# AutomatonXL320.net
KiCad netlist of a schematic drawn in EAGLE
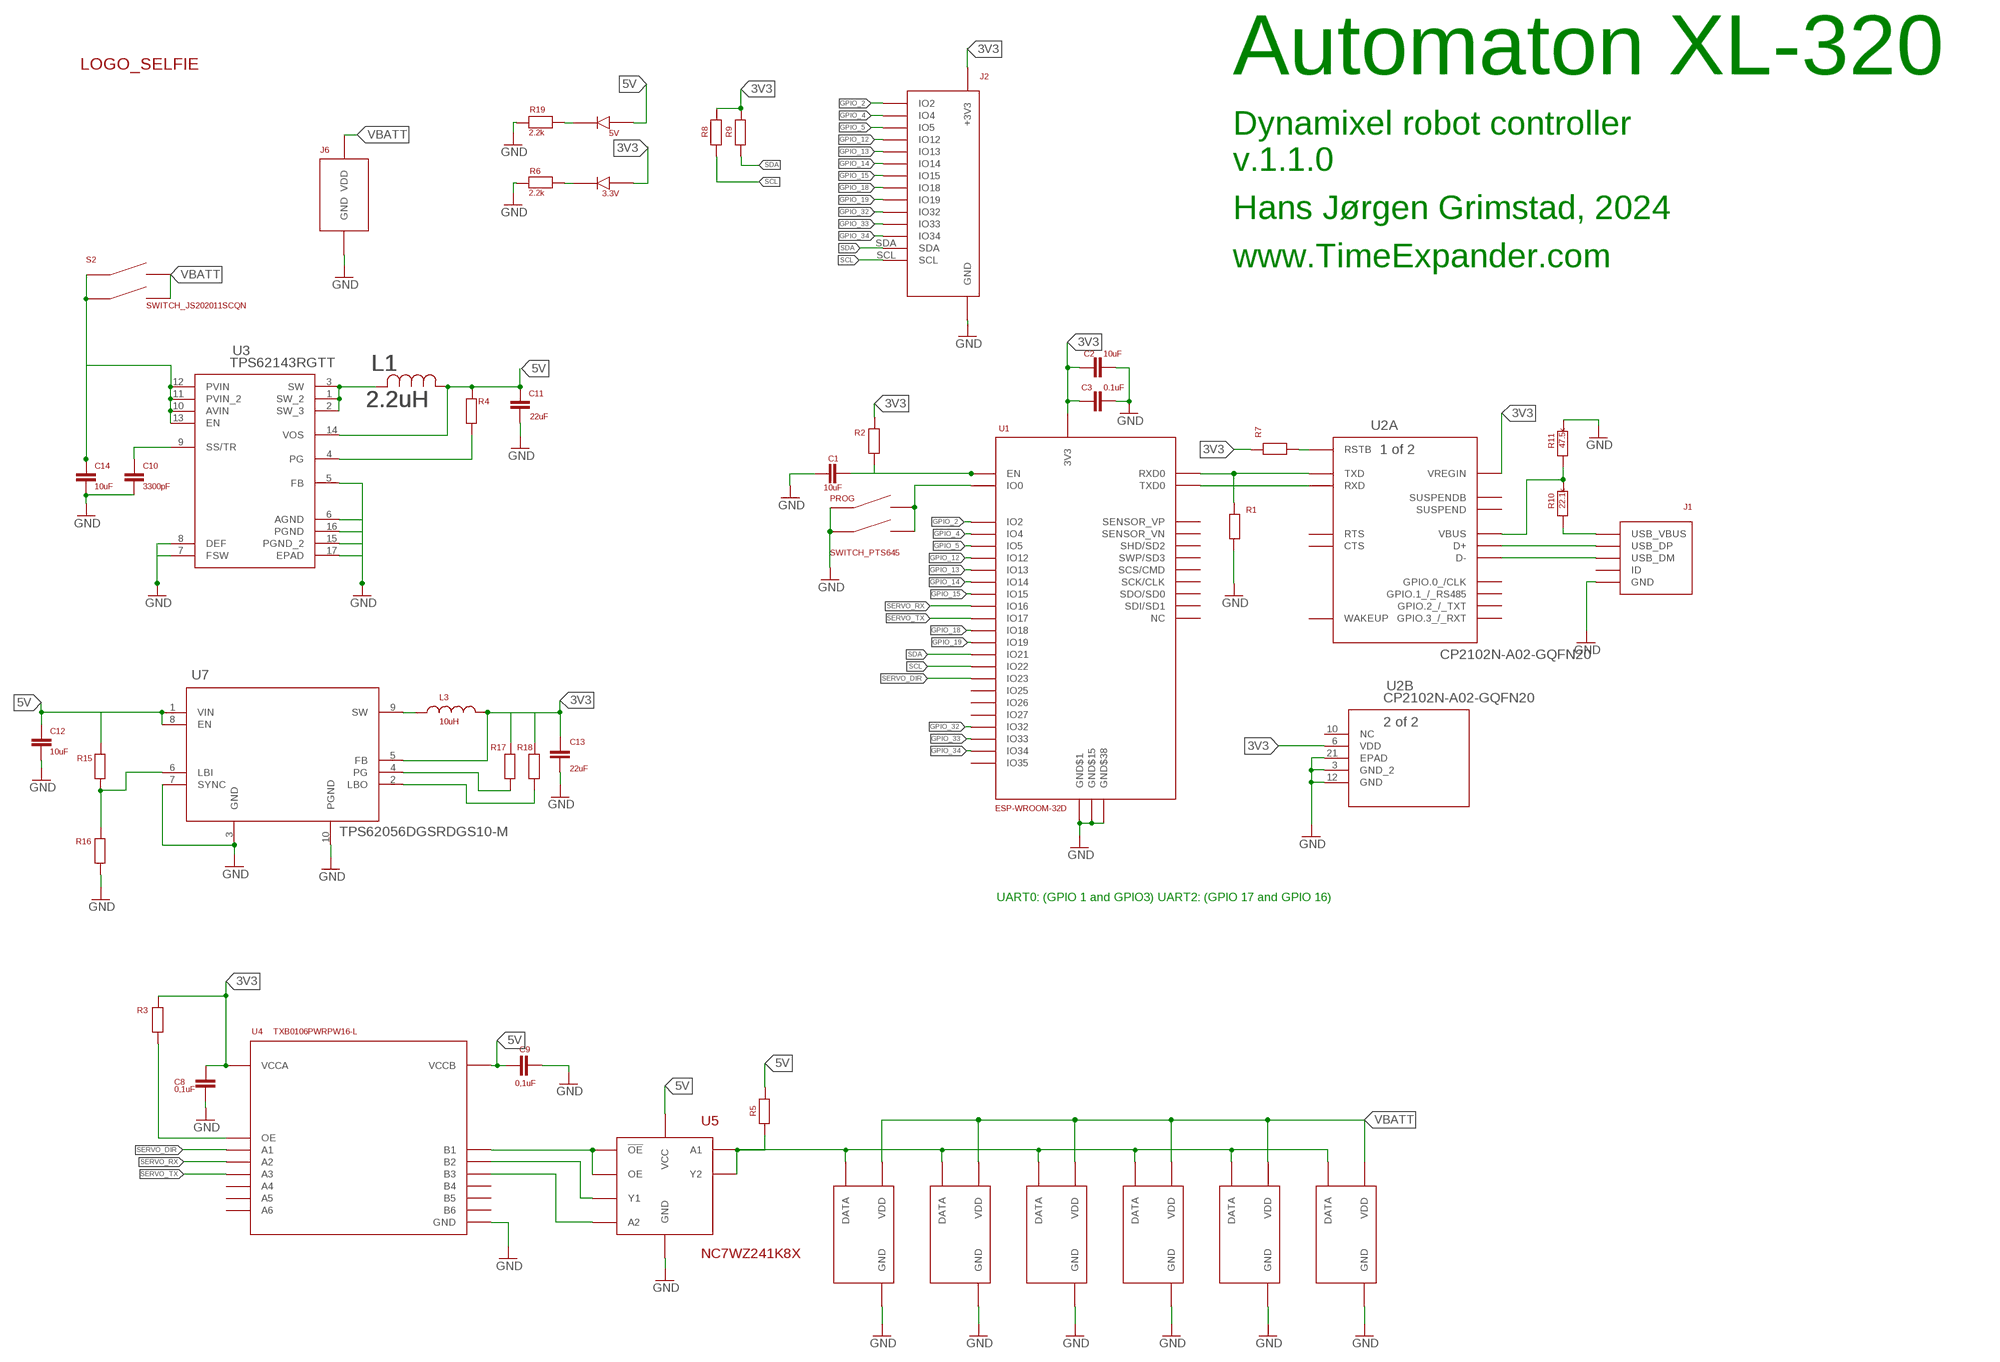
[diagram p0: schematic, sheet 1]

(export (version "E")
  (design (tool "Eeschema 10.0.6"))
  (components
    (comp (ref "3.3V")
      (value "LED_APTR3216PBC/A")
      (footprint "eagle-import:LED_APTR3216PBC_A")
      (libsource (lib "eagle-import") (part "LED_APTR3216PBC/A"))
    )
    (comp (ref "5V")
      (value "LED_APTR3216PBC/A")
      (footprint "eagle-import:LED_APTR3216PBC_A")
      (libsource (lib "eagle-import") (part "LED_APTR3216PBC/A"))
    )
    (comp (ref "C1")
      (value "10uF")
      (footprint "eagle-import:CAP_0402")
      (libsource (lib "eagle-import") (part "CAPACITOR0402"))
    )
    (comp (ref "C2")
      (value "10uF")
      (footprint "eagle-import:CAP_0402")
      (libsource (lib "eagle-import") (part "CAPACITOR0402"))
    )
    (comp (ref "C3")
      (value "0.1uF")
      (footprint "eagle-import:CAP_0402")
      (libsource (lib "eagle-import") (part "CAPACITOR0402"))
    )
    (comp (ref "C8")
      (value "0,1uF")
      (footprint "eagle-import:CAP_0402")
      (libsource (lib "eagle-import") (part "CAPACITOR0402"))
    )
    (comp (ref "C9")
      (value "0,1uF")
      (footprint "eagle-import:CAP_0402")
      (libsource (lib "eagle-import") (part "CAPACITOR0402"))
    )
    (comp (ref "C10")
      (value "3300pF")
      (footprint "eagle-import:CAP_0402")
      (libsource (lib "eagle-import") (part "CAPACITOR0402"))
    )
    (comp (ref "C11")
      (value "22uF")
      (footprint "eagle-import:CAP_1206")
      (libsource (lib "eagle-import") (part "CAPACITOR1206"))
    )
    (comp (ref "C12")
      (value "10uF")
      (footprint "eagle-import:CAP_1206")
      (libsource (lib "eagle-import") (part "CAPACITOR1206"))
    )
    (comp (ref "C13")
      (value "22uF")
      (footprint "eagle-import:CAP_1206")
      (libsource (lib "eagle-import") (part "CAPACITOR1206"))
    )
    (comp (ref "C14")
      (value "10uF")
      (footprint "eagle-import:CAP_1206")
      (libsource (lib "eagle-import") (part "CAPACITOR1206"))
    )
    (comp (ref "J1")
      (value "USB_RCPT_10118192-0001LF")
      (footprint "eagle-import:USB_RCPT_10118192-0001LF")
      (libsource (lib "eagle-import") (part "USB_RCPT_10118192-0001LF"))
    )
    (comp (ref "J2")
      (value "ESP_ROBOT_BOARD_GPIO_16")
      (footprint "eagle-import:ESP_ROBOT_BOARD_GPIO_16")
      (libsource (lib "eagle-import") (part "ESP_ROBOT_BOARD_GPIO_16"))
    )
    (comp (ref "J6")
      (value "BATTERY")
      (footprint "eagle-import:BATTERY_SOLDER_TERMINAL")
      (libsource (lib "eagle-import") (part "POWER_SOLDER_TERMINAL9V"))
    )
    (comp (ref "L1")
      (value "2.2uH")
      (footprint "eagle-import:IND_IHLP-1616AB-M")
      (fields (field (name "MANUFACTURER_PART_NUMBER") "IHLP1616ABER2R2M11"))
      (libsource (lib "eagle-import") (part "IHLP1616ABER2R2M11IND_IHLP-1616AB-M"))
    )
    (comp (ref "L3")
      (value "10uH")
      (footprint "eagle-import:IND_4028")
      (libsource (lib "eagle-import") (part "INDUCTOR_VLCF4024T-100MR90-2"))
    )
    (comp (ref "PROG")
      (value "SWITCH_PTS645")
      (footprint "eagle-import:SWITCH_PTS645_EE_NBIOT_01")
      (libsource (lib "eagle-import") (part "SWITCH_PTS645"))
    )
    (comp (ref "R1")
      (value "RESISTOR0402")
      (footprint "eagle-import:RES_0402")
      (libsource (lib "eagle-import") (part "RESISTOR0402"))
    )
    (comp (ref "R2")
      (value "RESISTOR0402")
      (footprint "eagle-import:RES_0402")
      (libsource (lib "eagle-import") (part "RESISTOR0402"))
    )
    (comp (ref "R3")
      (value "RESISTOR0402")
      (footprint "eagle-import:RES_0402")
      (libsource (lib "eagle-import") (part "RESISTOR0402"))
    )
    (comp (ref "R4")
      (value "RESISTOR0402")
      (footprint "eagle-import:RES_0402")
      (libsource (lib "eagle-import") (part "RESISTOR0402"))
    )
    (comp (ref "R5")
      (value "RESISTOR0402")
      (footprint "eagle-import:RES_0402")
      (libsource (lib "eagle-import") (part "RESISTOR0402"))
    )
    (comp (ref "R6")
      (value "2.2k")
      (footprint "eagle-import:RES_0402")
      (libsource (lib "eagle-import") (part "RESISTOR"))
    )
    (comp (ref "R7")
      (value "RESISTOR0402")
      (footprint "eagle-import:RES_0402")
      (libsource (lib "eagle-import") (part "RESISTOR0402"))
    )
    (comp (ref "R8")
      (value "RESISTOR0402")
      (footprint "eagle-import:RES_0402")
      (libsource (lib "eagle-import") (part "RESISTOR0402"))
    )
    (comp (ref "R9")
      (value "RESISTOR0402")
      (footprint "eagle-import:RES_0402")
      (libsource (lib "eagle-import") (part "RESISTOR0402"))
    )
    (comp (ref "R10")
      (value "22.1k")
      (footprint "eagle-import:RES_0402")
      (libsource (lib "eagle-import") (part "RESISTOR0402"))
    )
    (comp (ref "R11")
      (value "47.5k")
      (footprint "eagle-import:RES_0402")
      (libsource (lib "eagle-import") (part "RESISTOR0402"))
    )
    (comp (ref "R15")
      (value "RESISTOR0402")
      (footprint "eagle-import:RES_0402")
      (libsource (lib "eagle-import") (part "RESISTOR0402"))
    )
    (comp (ref "R16")
      (value "RESISTOR0402")
      (footprint "eagle-import:RES_0402")
      (libsource (lib "eagle-import") (part "RESISTOR0402"))
    )
    (comp (ref "R17")
      (value "RESISTOR0402")
      (footprint "eagle-import:RES_0402")
      (libsource (lib "eagle-import") (part "RESISTOR0402"))
    )
    (comp (ref "R18")
      (value "RESISTOR0402")
      (footprint "eagle-import:RES_0402")
      (libsource (lib "eagle-import") (part "RESISTOR0402"))
    )
    (comp (ref "R19")
      (value "2.2k")
      (footprint "eagle-import:RES_0402")
      (libsource (lib "eagle-import") (part "RESISTOR"))
    )
    (comp (ref "S2")
      (value "SWITCH_JS202011SCQN")
      (footprint "eagle-import:SWITCH_JS202011SCQN")
      (libsource (lib "eagle-import") (part "SWITCH_JS202011SCQN"))
    )
    (comp (ref "U$1")
      (value "DYNAMIXEL_MOLEX_MINISPOX_3P_HEADERXL-320")
      (footprint "eagle-import:DYNAMIXEL_MICROLATCH_3P_HEADER")
      (libsource (lib "eagle-import") (part "DYNAMIXEL_MOLEX_MINISPOX_3P_HEADERXL-320"))
    )
    (comp (ref "U$2")
      (value "LOGO_SELFIESELFIE_2")
      (footprint "eagle-import:TIMEEXPANDER_LOGO_1")
      (libsource (lib "eagle-import") (part "LOGO_SELFIESELFIE_2"))
    )
    (comp (ref "U$4")
      (value "DYNAMIXEL_MOLEX_MINISPOX_3P_HEADERXL-320")
      (footprint "eagle-import:DYNAMIXEL_MICROLATCH_3P_HEADER")
      (libsource (lib "eagle-import") (part "DYNAMIXEL_MOLEX_MINISPOX_3P_HEADERXL-320"))
    )
    (comp (ref "U$5")
      (value "DYNAMIXEL_MOLEX_MINISPOX_3P_HEADERXL-320")
      (footprint "eagle-import:DYNAMIXEL_MICROLATCH_3P_HEADER")
      (libsource (lib "eagle-import") (part "DYNAMIXEL_MOLEX_MINISPOX_3P_HEADERXL-320"))
    )
    (comp (ref "U$6")
      (value "DYNAMIXEL_MOLEX_MINISPOX_3P_HEADERXL-320")
      (footprint "eagle-import:DYNAMIXEL_MICROLATCH_3P_HEADER")
      (libsource (lib "eagle-import") (part "DYNAMIXEL_MOLEX_MINISPOX_3P_HEADERXL-320"))
    )
    (comp (ref "U$8")
      (value "DYNAMIXEL_MOLEX_MINISPOX_3P_HEADERXL-320")
      (footprint "eagle-import:DYNAMIXEL_MICROLATCH_3P_HEADER")
      (libsource (lib "eagle-import") (part "DYNAMIXEL_MOLEX_MINISPOX_3P_HEADERXL-320"))
    )
    (comp (ref "U$9")
      (value "DYNAMIXEL_MOLEX_MINISPOX_3P_HEADERXL-320")
      (footprint "eagle-import:DYNAMIXEL_MICROLATCH_3P_HEADER")
      (libsource (lib "eagle-import") (part "DYNAMIXEL_MOLEX_MINISPOX_3P_HEADERXL-320"))
    )
    (comp (ref "U1")
      (value "ESP-WROOM-32D")
      (footprint "eagle-import:ESP_WROOM_32D")
      (libsource (lib "eagle-import") (part "ESP-WROOM-32D"))
    )
    (comp (ref "U2")
      (value "CP2102N-A02-GQFN20")
      (footprint "eagle-import:QFN20_CP2102N_SIL")
      (fields (field (name "COPYRIGHT") "Copyright (C) 2023 Ultra Librarian. All rights reserved."))
      (libsource (lib "eagle-import") (part "CP2102N-A02-GQFN20"))
    )
    (comp (ref "U3")
      (value "TPS62143RGTT")
      (footprint "eagle-import:RGT16_1P7X1P7")
      (fields (field (name "MANUFACTURER") "Texas Instruments"))
      (libsource (lib "eagle-import") (part "TPS62143RGTT"))
    )
    (comp (ref "U4")
      (value "TXB0106PWRPW16-L")
      (footprint "eagle-import:PW16-L")
      (fields (field (name "MANUFACTURER_PART_NUMBER") "TXB0106PWR"))
      (libsource (lib "eagle-import") (part "TXB0106PWRPW16-L"))
    )
    (comp (ref "U5")
      (value "NC7WZ241K8X")
      (footprint "eagle-import:NC7WZ241K8X")
      (libsource (lib "eagle-import") (part "NC7WZ241K8X"))
    )
    (comp (ref "U7")
      (value "TPS62056DGSRDGS10-M")
      (footprint "eagle-import:DGS10-M")
      (fields
        (field (name "MANUFACTURER") "Texas Instruments")
        (field (name "MANUFACTURER_PART_NUMBER") "TPS62056DGSR")
      )
      (libsource (lib "eagle-import") (part "TPS62056DGSRDGS10-M"))
    )
  )
  (nets
    (net (code "1") (name "3V3") (class "Default")
      (node (ref "3.3V") (pin "A") (pinfunction "A_A") (pintype "passive"))
      (node (ref "C13") (pin "P$1") (pinfunction "1_P$1") (pintype "passive"))
      (node (ref "C2") (pin "P$1") (pinfunction "1_P$1") (pintype "passive"))
      (node (ref "C3") (pin "P$1") (pinfunction "1_P$1") (pintype "passive"))
      (node (ref "C8") (pin "P$2") (pinfunction "2_P$2") (pintype "passive"))
      (node (ref "J2") (pin "+3V3") (pinfunction "+3V3_+3V3") (pintype "bidirectional"))
      (node (ref "L3") (pin "2") (pinfunction "2_2") (pintype "passive"))
      (node (ref "R17") (pin "P$2") (pinfunction "P$2_P$2") (pintype "bidirectional"))
      (node (ref "R18") (pin "P$2") (pinfunction "P$2_P$2") (pintype "bidirectional"))
      (node (ref "R2") (pin "P$2") (pinfunction "P$2_P$2") (pintype "bidirectional"))
      (node (ref "R3") (pin "P$2") (pinfunction "P$2_P$2") (pintype "bidirectional"))
      (node (ref "R7") (pin "P$1") (pinfunction "P$1_P$1") (pintype "bidirectional"))
      (node (ref "R8") (pin "P$2") (pinfunction "P$2_P$2") (pintype "bidirectional"))
      (node (ref "R9") (pin "P$2") (pinfunction "P$2_P$2") (pintype "bidirectional"))
      (node (ref "U1") (pin "2") (pinfunction "3V3_2") (pintype "bidirectional"))
      (node (ref "U2") (pin "6") (pinfunction "VDD_6") (pintype "power_in"))
      (node (ref "U2") (pin "7") (pinfunction "VREGIN_7") (pintype "passive"))
      (node (ref "U4") (pin "2") (pinfunction "VCCA_2") (pintype "power_in"))
      (node (ref "U7") (pin "5") (pinfunction "FB_5") (pintype "input"))
    )
    (net (code "2") (name "5V") (class "Default")
      (node (ref "5V") (pin "A") (pinfunction "A_A") (pintype "passive"))
      (node (ref "C11") (pin "P$1") (pinfunction "1_P$1") (pintype "passive"))
      (node (ref "C12") (pin "P$1") (pinfunction "1_P$1") (pintype "passive"))
      (node (ref "C9") (pin "P$1") (pinfunction "1_P$1") (pintype "passive"))
      (node (ref "L1") (pin "1") (pinfunction "1_1") (pintype "passive"))
      (node (ref "R15") (pin "P$2") (pinfunction "P$2_P$2") (pintype "bidirectional"))
      (node (ref "R4") (pin "P$2") (pinfunction "P$2_P$2") (pintype "bidirectional"))
      (node (ref "R5") (pin "P$2") (pinfunction "P$2_P$2") (pintype "bidirectional"))
      (node (ref "U3") (pin "14") (pinfunction "VOS_14") (pintype "input"))
      (node (ref "U4") (pin "15") (pinfunction "VCCB_15") (pintype "power_in"))
      (node (ref "U5") (pin "VCC") (pinfunction "VCC_VCC") (pintype "power_in"))
      (node (ref "U7") (pin "1") (pinfunction "VIN_1") (pintype "input"))
      (node (ref "U7") (pin "8") (pinfunction "EN_8") (pintype "input"))
    )
    (net (code "3") (name "GND") (class "Default")
      (node (ref "C1") (pin "P$1") (pinfunction "1_P$1") (pintype "passive"))
      (node (ref "C10") (pin "P$2") (pinfunction "2_P$2") (pintype "passive"))
      (node (ref "C11") (pin "P$2") (pinfunction "2_P$2") (pintype "passive"))
      (node (ref "C12") (pin "P$2") (pinfunction "2_P$2") (pintype "passive"))
      (node (ref "C13") (pin "P$2") (pinfunction "2_P$2") (pintype "passive"))
      (node (ref "C14") (pin "P$2") (pinfunction "2_P$2") (pintype "passive"))
      (node (ref "C2") (pin "P$2") (pinfunction "2_P$2") (pintype "passive"))
      (node (ref "C3") (pin "P$2") (pinfunction "2_P$2") (pintype "passive"))
      (node (ref "C8") (pin "P$1") (pinfunction "1_P$1") (pintype "passive"))
      (node (ref "C9") (pin "P$2") (pinfunction "2_P$2") (pintype "passive"))
      (node (ref "J1") (pin "GND") (pinfunction "GND_GND") (pintype "passive"))
      (node (ref "J2") (pin "GND") (pinfunction "GND_GND") (pintype "bidirectional"))
      (node (ref "J6") (pin "-") (pinfunction "GND_-") (pintype "bidirectional"))
      (node (ref "PROG") (pin "A1") (pinfunction "A1_A1") (pintype "bidirectional"))
      (node (ref "PROG") (pin "A2") (pinfunction "A2_A2") (pintype "bidirectional"))
      (node (ref "R1") (pin "P$2") (pinfunction "P$2_P$2") (pintype "bidirectional"))
      (node (ref "R11") (pin "P$2") (pinfunction "P$2_P$2") (pintype "bidirectional"))
      (node (ref "R16") (pin "P$1") (pinfunction "P$1_P$1") (pintype "bidirectional"))
      (node (ref "R19") (pin "P$1") (pinfunction "P$1_P$1") (pintype "bidirectional"))
      (node (ref "R6") (pin "P$1") (pinfunction "P$1_P$1") (pintype "bidirectional"))
      (node (ref "U$1") (pin "GND") (pinfunction "GND_GND") (pintype "bidirectional"))
      (node (ref "U$4") (pin "GND") (pinfunction "GND_GND") (pintype "bidirectional"))
      (node (ref "U$5") (pin "GND") (pinfunction "GND_GND") (pintype "bidirectional"))
      (node (ref "U$6") (pin "GND") (pinfunction "GND_GND") (pintype "bidirectional"))
      (node (ref "U$8") (pin "GND") (pinfunction "GND_GND") (pintype "bidirectional"))
      (node (ref "U$9") (pin "GND") (pinfunction "GND_GND") (pintype "bidirectional"))
      (node (ref "U1") (pin "1") (pinfunction "GND$1_1") (pintype "bidirectional"))
      (node (ref "U1") (pin "15") (pinfunction "GND$15_15") (pintype "bidirectional"))
      (node (ref "U1") (pin "38") (pinfunction "GND$38_38") (pintype "bidirectional"))
      (node (ref "U1") (pin "GND$39") (pinfunction "GND$38_GND$39") (pintype "bidirectional"))
      (node (ref "U1") (pin "GND$40") (pinfunction "GND$38_GND$40") (pintype "bidirectional"))
      (node (ref "U1") (pin "GND$41") (pinfunction "GND$38_GND$41") (pintype "bidirectional"))
      (node (ref "U1") (pin "GND$42") (pinfunction "GND$38_GND$42") (pintype "bidirectional"))
      (node (ref "U1") (pin "GND$43") (pinfunction "GND$38_GND$43") (pintype "bidirectional"))
      (node (ref "U1") (pin "GND$44") (pinfunction "GND$38_GND$44") (pintype "bidirectional"))
      (node (ref "U1") (pin "GND$45") (pinfunction "GND$38_GND$45") (pintype "bidirectional"))
      (node (ref "U1") (pin "GND$46") (pinfunction "GND$38_GND$46") (pintype "bidirectional"))
      (node (ref "U1") (pin "GND$47") (pinfunction "GND$38_GND$47") (pintype "bidirectional"))
      (node (ref "U2") (pin "12") (pinfunction "GND_12") (pintype "passive"))
      (node (ref "U2") (pin "21") (pinfunction "EPAD_21") (pintype "passive"))
      (node (ref "U2") (pin "3") (pinfunction "GND_2_3") (pintype "passive"))
      (node (ref "U3") (pin "15") (pinfunction "PGND_2_15") (pintype "power_in"))
      (node (ref "U3") (pin "16") (pinfunction "PGND_16") (pintype "power_in"))
      (node (ref "U3") (pin "17") (pinfunction "EPAD_17") (pintype "passive"))
      (node (ref "U3") (pin "5") (pinfunction "FB_5") (pintype "input"))
      (node (ref "U3") (pin "6") (pinfunction "AGND_6") (pintype "power_in"))
      (node (ref "U3") (pin "7") (pinfunction "FSW_7") (pintype "input"))
      (node (ref "U3") (pin "8") (pinfunction "DEF_8") (pintype "input"))
      (node (ref "U4") (pin "9") (pinfunction "GND_9") (pintype "power_in"))
      (node (ref "U5") (pin "GND") (pinfunction "GND_GND") (pintype "power_in"))
      (node (ref "U7") (pin "10") (pinfunction "PGND_10") (pintype "input"))
      (node (ref "U7") (pin "3") (pinfunction "GND_3") (pintype "input"))
      (node (ref "U7") (pin "7") (pinfunction "SYNC_7") (pintype "input"))
    )
    (net (code "4") (name "GPIO_2") (class "Default")
      (node (ref "J2") (pin "IO2") (pinfunction "IO2_IO2") (pintype "bidirectional"))
      (node (ref "U1") (pin "24") (pinfunction "IO2_24") (pintype "bidirectional"))
    )
    (net (code "5") (name "GPIO_4") (class "Default")
      (node (ref "J2") (pin "IO4") (pinfunction "IO4_IO4") (pintype "bidirectional"))
      (node (ref "U1") (pin "26") (pinfunction "IO4_26") (pintype "bidirectional"))
    )
    (net (code "6") (name "GPIO_5") (class "Default")
      (node (ref "J2") (pin "IO5") (pinfunction "IO5_IO5") (pintype "bidirectional"))
      (node (ref "U1") (pin "29") (pinfunction "IO5_29") (pintype "bidirectional"))
    )
    (net (code "7") (name "GPIO_12") (class "Default")
      (node (ref "J2") (pin "IO12") (pinfunction "IO12_IO12") (pintype "bidirectional"))
      (node (ref "U1") (pin "14") (pinfunction "IO12_14") (pintype "bidirectional"))
    )
    (net (code "8") (name "GPIO_13") (class "Default")
      (node (ref "J2") (pin "IO13") (pinfunction "IO13_IO13") (pintype "bidirectional"))
      (node (ref "U1") (pin "16") (pinfunction "IO13_16") (pintype "bidirectional"))
    )
    (net (code "9") (name "GPIO_14") (class "Default")
      (node (ref "J2") (pin "IO14") (pinfunction "IO14_IO14") (pintype "bidirectional"))
      (node (ref "U1") (pin "13") (pinfunction "IO14_13") (pintype "bidirectional"))
    )
    (net (code "10") (name "GPIO_15") (class "Default")
      (node (ref "J2") (pin "IO15") (pinfunction "IO15_IO15") (pintype "bidirectional"))
      (node (ref "U1") (pin "23") (pinfunction "IO15_23") (pintype "bidirectional"))
    )
    (net (code "11") (name "GPIO_18") (class "Default")
      (node (ref "J2") (pin "IO18") (pinfunction "IO18_IO18") (pintype "bidirectional"))
      (node (ref "U1") (pin "30") (pinfunction "IO18_30") (pintype "bidirectional"))
    )
    (net (code "12") (name "GPIO_19") (class "Default")
      (node (ref "J2") (pin "IO19") (pinfunction "IO19_IO19") (pintype "bidirectional"))
      (node (ref "U1") (pin "31") (pinfunction "IO19_31") (pintype "bidirectional"))
    )
    (net (code "13") (name "GPIO_32") (class "Default")
      (node (ref "J2") (pin "IO32") (pinfunction "IO32_IO32") (pintype "bidirectional"))
      (node (ref "U1") (pin "8") (pinfunction "IO32_8") (pintype "bidirectional"))
    )
    (net (code "14") (name "GPIO_33") (class "Default")
      (node (ref "J2") (pin "IO33") (pinfunction "IO33_IO33") (pintype "bidirectional"))
      (node (ref "U1") (pin "9") (pinfunction "IO33_9") (pintype "bidirectional"))
    )
    (net (code "15") (name "GPIO_34") (class "Default")
      (node (ref "J2") (pin "IO34") (pinfunction "IO34_IO34") (pintype "bidirectional"))
      (node (ref "U1") (pin "6") (pinfunction "IO34_6") (pintype "bidirectional"))
    )
    (net (code "16") (name "Net-(3.3V-PadC)") (class "Default")
      (node (ref "3.3V") (pin "C") (pinfunction "C_C") (pintype "passive"))
      (node (ref "R6") (pin "P$2") (pinfunction "P$2_P$2") (pintype "bidirectional"))
    )
    (net (code "17") (name "Net-(5V-PadC)") (class "Default")
      (node (ref "5V") (pin "C") (pinfunction "C_C") (pintype "passive"))
      (node (ref "R19") (pin "P$2") (pinfunction "P$2_P$2") (pintype "bidirectional"))
    )
    (net (code "18") (name "Net-(C1-2)") (class "Default")
      (node (ref "C1") (pin "P$2") (pinfunction "2_P$2") (pintype "passive"))
      (node (ref "R2") (pin "P$1") (pinfunction "P$1_P$1") (pintype "bidirectional"))
      (node (ref "U1") (pin "3") (pinfunction "EN_3") (pintype "bidirectional"))
    )
    (net (code "19") (name "Net-(C10-1)") (class "Default")
      (node (ref "C10") (pin "P$1") (pinfunction "1_P$1") (pintype "passive"))
      (node (ref "U3") (pin "9") (pinfunction "SS/TR_9") (pintype "input"))
    )
    (net (code "20") (name "Net-(C14-1)") (class "Default")
      (node (ref "C14") (pin "P$1") (pinfunction "1_P$1") (pintype "passive"))
      (node (ref "S2") (pin "2") (pinfunction "A2_2") (pintype "bidirectional"))
      (node (ref "S2") (pin "5") (pinfunction "A1_5") (pintype "bidirectional"))
      (node (ref "U3") (pin "10") (pinfunction "AVIN_10") (pintype "input"))
      (node (ref "U3") (pin "11") (pinfunction "PVIN_2_11") (pintype "input"))
      (node (ref "U3") (pin "12") (pinfunction "PVIN_12") (pintype "input"))
      (node (ref "U3") (pin "13") (pinfunction "EN_13") (pintype "input"))
    )
    (net (code "21") (name "Net-(J1-USB_DM)") (class "Default")
      (node (ref "J1") (pin "D-") (pinfunction "USB_DM_D-") (pintype "passive"))
      (node (ref "U2") (pin "5") (pinfunction "D-_5") (pintype "passive"))
    )
    (net (code "22") (name "Net-(J1-USB_DP)") (class "Default")
      (node (ref "J1") (pin "D+") (pinfunction "USB_DP_D+") (pintype "passive"))
      (node (ref "U2") (pin "4") (pinfunction "D+_4") (pintype "passive"))
    )
    (net (code "23") (name "Net-(J1-USB_VBUS)") (class "Default")
      (node (ref "J1") (pin "VCC") (pinfunction "USB_VBUS_VCC") (pintype "passive"))
      (node (ref "R10") (pin "P$1") (pinfunction "P$1_P$1") (pintype "bidirectional"))
    )
    (net (code "24") (name "Net-(R5-PadP$1)") (class "Default")
      (node (ref "R5") (pin "P$1") (pinfunction "P$1_P$1") (pintype "bidirectional"))
      (node (ref "U$1") (pin "DATA") (pinfunction "DATA_DATA") (pintype "bidirectional"))
      (node (ref "U$4") (pin "DATA") (pinfunction "DATA_DATA") (pintype "bidirectional"))
      (node (ref "U$5") (pin "DATA") (pinfunction "DATA_DATA") (pintype "bidirectional"))
      (node (ref "U$6") (pin "DATA") (pinfunction "DATA_DATA") (pintype "bidirectional"))
      (node (ref "U$8") (pin "DATA") (pinfunction "DATA_DATA") (pintype "bidirectional"))
      (node (ref "U$9") (pin "DATA") (pinfunction "DATA_DATA") (pintype "bidirectional"))
      (node (ref "U5") (pin "A1") (pinfunction "A1_A1") (pintype "power_in"))
      (node (ref "U5") (pin "Y2") (pinfunction "Y2_Y2") (pintype "power_in"))
    )
    (net (code "25") (name "Net-(U1-IO0)") (class "Default")
      (node (ref "PROG") (pin "B1") (pinfunction "B1_B1") (pintype "bidirectional"))
      (node (ref "PROG") (pin "B2") (pinfunction "B2_B2") (pintype "bidirectional"))
      (node (ref "U1") (pin "25") (pinfunction "IO0_25") (pintype "bidirectional"))
    )
    (net (code "26") (name "Net-(U1-RXD0)") (class "Default")
      (node (ref "R1") (pin "P$1") (pinfunction "P$1_P$1") (pintype "bidirectional"))
      (node (ref "U1") (pin "34") (pinfunction "RXD0_34") (pintype "bidirectional"))
      (node (ref "U2") (pin "18") (pinfunction "TXD_18") (pintype "passive"))
    )
    (net (code "27") (name "Net-(U1-TXD0)") (class "Default")
      (node (ref "U1") (pin "35") (pinfunction "TXD0_35") (pintype "bidirectional"))
      (node (ref "U2") (pin "17") (pinfunction "RXD_17") (pintype "passive"))
    )
    (net (code "28") (name "Net-(U2A-RSTB)") (class "Default")
      (node (ref "R7") (pin "P$2") (pinfunction "P$2_P$2") (pintype "bidirectional"))
      (node (ref "U2") (pin "9") (pinfunction "RSTB_9") (pintype "passive"))
    )
    (net (code "29") (name "Net-(U2A-VBUS)") (class "Default")
      (node (ref "R10") (pin "P$2") (pinfunction "P$2_P$2") (pintype "bidirectional"))
      (node (ref "R11") (pin "P$1") (pinfunction "P$1_P$1") (pintype "bidirectional"))
      (node (ref "U2") (pin "8") (pinfunction "VBUS_8") (pintype "passive"))
    )
    (net (code "30") (name "Net-(U3-PG)") (class "Default")
      (node (ref "R4") (pin "P$1") (pinfunction "P$1_P$1") (pintype "bidirectional"))
      (node (ref "U3") (pin "4") (pinfunction "PG_4") (pintype "output"))
    )
    (net (code "31") (name "Net-(U3-SW)") (class "Default")
      (node (ref "L1") (pin "2") (pinfunction "2_2") (pintype "passive"))
      (node (ref "U3") (pin "1") (pinfunction "SW_2_1") (pintype "output"))
      (node (ref "U3") (pin "2") (pinfunction "SW_3_2") (pintype "output"))
      (node (ref "U3") (pin "3") (pinfunction "SW_3") (pintype "output"))
    )
    (net (code "32") (name "Net-(U4-B1)") (class "Default")
      (node (ref "U4") (pin "16") (pinfunction "B1_16") (pintype "bidirectional"))
      (node (ref "U5") (pin "!OE") (pinfunction "~{OE}_!OE") (pintype "power_in"))
      (node (ref "U5") (pin "OE") (pinfunction "OE_OE") (pintype "power_in"))
    )
    (net (code "33") (name "Net-(U4-B2)") (class "Default")
      (node (ref "U4") (pin "14") (pinfunction "B2_14") (pintype "bidirectional"))
      (node (ref "U5") (pin "Y1") (pinfunction "Y1_Y1") (pintype "power_in"))
    )
    (net (code "34") (name "Net-(U4-B3)") (class "Default")
      (node (ref "U4") (pin "13") (pinfunction "B3_13") (pintype "bidirectional"))
      (node (ref "U5") (pin "A2") (pinfunction "A2_A2") (pintype "power_in"))
    )
    (net (code "35") (name "Net-(U4-OE)") (class "Default")
      (node (ref "R3") (pin "P$1") (pinfunction "P$1_P$1") (pintype "bidirectional"))
      (node (ref "U4") (pin "8") (pinfunction "OE_8") (pintype "output"))
    )
    (net (code "36") (name "Net-(U7-LBI)") (class "Default")
      (node (ref "R15") (pin "P$1") (pinfunction "P$1_P$1") (pintype "bidirectional"))
      (node (ref "R16") (pin "P$2") (pinfunction "P$2_P$2") (pintype "bidirectional"))
      (node (ref "U7") (pin "6") (pinfunction "LBI_6") (pintype "input"))
    )
    (net (code "37") (name "Net-(U7-LBO)") (class "Default")
      (node (ref "R18") (pin "P$1") (pinfunction "P$1_P$1") (pintype "bidirectional"))
      (node (ref "U7") (pin "2") (pinfunction "LBO_2") (pintype "output"))
    )
    (net (code "38") (name "Net-(U7-PG)") (class "Default")
      (node (ref "R17") (pin "P$1") (pinfunction "P$1_P$1") (pintype "bidirectional"))
      (node (ref "U7") (pin "4") (pinfunction "PG_4") (pintype "output"))
    )
    (net (code "39") (name "Net-(U7-SW)") (class "Default")
      (node (ref "L3") (pin "1") (pinfunction "1_1") (pintype "passive"))
      (node (ref "U7") (pin "9") (pinfunction "SW_9") (pintype "output"))
    )
    (net (code "40") (name "SCL") (class "Default")
      (node (ref "J2") (pin "SCL") (pinfunction "SCL_SCL") (pintype "bidirectional"))
      (node (ref "R8") (pin "P$1") (pinfunction "P$1_P$1") (pintype "bidirectional"))
      (node (ref "U1") (pin "36") (pinfunction "IO22_36") (pintype "bidirectional"))
    )
    (net (code "41") (name "SDA") (class "Default")
      (node (ref "J2") (pin "SDA") (pinfunction "SDA_SDA") (pintype "bidirectional"))
      (node (ref "R9") (pin "P$1") (pinfunction "P$1_P$1") (pintype "bidirectional"))
      (node (ref "U1") (pin "33") (pinfunction "IO21_33") (pintype "bidirectional"))
    )
    (net (code "42") (name "SERVO_DIR") (class "Default")
      (node (ref "U1") (pin "37") (pinfunction "IO23_37") (pintype "bidirectional"))
      (node (ref "U4") (pin "1") (pinfunction "A1_1") (pintype "bidirectional"))
    )
    (net (code "43") (name "SERVO_RX") (class "Default")
      (node (ref "U1") (pin "27") (pinfunction "IO16_27") (pintype "bidirectional"))
      (node (ref "U4") (pin "3") (pinfunction "A2_3") (pintype "bidirectional"))
    )
    (net (code "44") (name "SERVO_TX") (class "Default")
      (node (ref "U1") (pin "28") (pinfunction "IO17_28") (pintype "bidirectional"))
      (node (ref "U4") (pin "4") (pinfunction "A3_4") (pintype "bidirectional"))
    )
    (net (code "45") (name "VBATT") (class "Default")
      (node (ref "J6") (pin "+") (pinfunction "VDD_+") (pintype "bidirectional"))
      (node (ref "S2") (pin "3") (pinfunction "B2_3") (pintype "bidirectional"))
      (node (ref "S2") (pin "6") (pinfunction "B1_6") (pintype "bidirectional"))
      (node (ref "U$1") (pin "VDD") (pinfunction "VDD_VDD") (pintype "bidirectional"))
      (node (ref "U$4") (pin "VDD") (pinfunction "VDD_VDD") (pintype "bidirectional"))
      (node (ref "U$5") (pin "VDD") (pinfunction "VDD_VDD") (pintype "bidirectional"))
      (node (ref "U$6") (pin "VDD") (pinfunction "VDD_VDD") (pintype "bidirectional"))
      (node (ref "U$8") (pin "VDD") (pinfunction "VDD_VDD") (pintype "bidirectional"))
      (node (ref "U$9") (pin "VDD") (pinfunction "VDD_VDD") (pintype "bidirectional"))
    )
    (net (code "46") (name "unconnected-(J1-PadID)") (class "Default")
      (node (ref "J1") (pin "ID") (pinfunction "ID_ID") (pintype "passive"))
    )
    (net (code "47") (name "unconnected-(U1-IO25-Pad10)") (class "Default")
      (node (ref "U1") (pin "10") (pinfunction "IO25_10") (pintype "bidirectional"))
    )
    (net (code "48") (name "unconnected-(U1-IO26-Pad11)") (class "Default")
      (node (ref "U1") (pin "11") (pinfunction "IO26_11") (pintype "bidirectional"))
    )
    (net (code "49") (name "unconnected-(U1-IO27-Pad12)") (class "Default")
      (node (ref "U1") (pin "12") (pinfunction "IO27_12") (pintype "bidirectional"))
    )
    (net (code "50") (name "unconnected-(U1-IO35-Pad7)") (class "Default")
      (node (ref "U1") (pin "7") (pinfunction "IO35_7") (pintype "bidirectional"))
    )
    (net (code "51") (name "unconnected-(U1-NC-Pad32)") (class "Default")
      (node (ref "U1") (pin "32") (pinfunction "NC_32") (pintype "bidirectional"))
    )
    (net (code "52") (name "unconnected-(U1-SCK{slash}CLK-Pad20)") (class "Default")
      (node (ref "U1") (pin "20") (pinfunction "SCK/CLK_20") (pintype "bidirectional"))
    )
    (net (code "53") (name "unconnected-(U1-SCS{slash}CMD-Pad19)") (class "Default")
      (node (ref "U1") (pin "19") (pinfunction "SCS/CMD_19") (pintype "bidirectional"))
    )
    (net (code "54") (name "unconnected-(U1-SDI{slash}SD1-Pad22)") (class "Default")
      (node (ref "U1") (pin "22") (pinfunction "SDI/SD1_22") (pintype "bidirectional"))
    )
    (net (code "55") (name "unconnected-(U1-SDO{slash}SD0-Pad21)") (class "Default")
      (node (ref "U1") (pin "21") (pinfunction "SDO/SD0_21") (pintype "bidirectional"))
    )
    (net (code "56") (name "unconnected-(U1-SENSOR_VN-Pad5)") (class "Default")
      (node (ref "U1") (pin "5") (pinfunction "SENSOR_VN_5") (pintype "bidirectional"))
    )
    (net (code "57") (name "unconnected-(U1-SENSOR_VP-Pad4)") (class "Default")
      (node (ref "U1") (pin "4") (pinfunction "SENSOR_VP_4") (pintype "bidirectional"))
    )
    (net (code "58") (name "unconnected-(U1-SHD{slash}SD2-Pad17)") (class "Default")
      (node (ref "U1") (pin "17") (pinfunction "SHD/SD2_17") (pintype "bidirectional"))
    )
    (net (code "59") (name "unconnected-(U1-SWP{slash}SD3-Pad18)") (class "Default")
      (node (ref "U1") (pin "18") (pinfunction "SWP/SD3_18") (pintype "bidirectional"))
    )
    (net (code "60") (name "unconnected-(U2A-CTS-Pad15)") (class "Default")
      (node (ref "U2") (pin "15") (pinfunction "CTS_15") (pintype "passive"))
    )
    (net (code "61") (name "unconnected-(U2A-GPIO.0_{slash}CLK-Pad2)") (class "Default")
      (node (ref "U2") (pin "2") (pinfunction "GPIO.0_/CLK_2") (pintype "bidirectional"))
    )
    (net (code "62") (name "unconnected-(U2A-GPIO.1_{slash}_RS485-Pad1)") (class "Default")
      (node (ref "U2") (pin "1") (pinfunction "GPIO.1_/_RS485_1") (pintype "bidirectional"))
    )
    (net (code "63") (name "unconnected-(U2A-GPIO.2_{slash}_TXT-Pad20)") (class "Default")
      (node (ref "U2") (pin "20") (pinfunction "GPIO.2_/_TXT_20") (pintype "bidirectional"))
    )
    (net (code "64") (name "unconnected-(U2A-GPIO.3_{slash}_RXT-Pad19)") (class "Default")
      (node (ref "U2") (pin "19") (pinfunction "GPIO.3_/_RXT_19") (pintype "bidirectional"))
    )
    (net (code "65") (name "unconnected-(U2A-RTS-Pad16)") (class "Default")
      (node (ref "U2") (pin "16") (pinfunction "RTS_16") (pintype "passive"))
    )
    (net (code "66") (name "unconnected-(U2A-SUSPEND-Pad14)") (class "Default")
      (node (ref "U2") (pin "14") (pinfunction "SUSPEND_14") (pintype "passive"))
    )
    (net (code "67") (name "unconnected-(U2A-SUSPENDB-Pad11)") (class "Default")
      (node (ref "U2") (pin "11") (pinfunction "SUSPENDB_11") (pintype "passive"))
    )
    (net (code "68") (name "unconnected-(U2A-WAKEUP-Pad13)") (class "Default")
      (node (ref "U2") (pin "13") (pinfunction "WAKEUP_13") (pintype "passive"))
    )
    (net (code "69") (name "unconnected-(U2B-NC-Pad10)") (class "Default")
      (node (ref "U2") (pin "10") (pinfunction "NC_10") (pintype "no_connect"))
    )
    (net (code "70") (name "unconnected-(U4-A4-Pad5)") (class "Default")
      (node (ref "U4") (pin "5") (pinfunction "A4_5") (pintype "bidirectional"))
    )
    (net (code "71") (name "unconnected-(U4-A5-Pad6)") (class "Default")
      (node (ref "U4") (pin "6") (pinfunction "A5_6") (pintype "bidirectional"))
    )
    (net (code "72") (name "unconnected-(U4-A6-Pad7)") (class "Default")
      (node (ref "U4") (pin "7") (pinfunction "A6_7") (pintype "bidirectional"))
    )
    (net (code "73") (name "unconnected-(U4-B4-Pad12)") (class "Default")
      (node (ref "U4") (pin "12") (pinfunction "B4_12") (pintype "bidirectional"))
    )
    (net (code "74") (name "unconnected-(U4-B5-Pad11)") (class "Default")
      (node (ref "U4") (pin "11") (pinfunction "B5_11") (pintype "bidirectional"))
    )
    (net (code "75") (name "unconnected-(U4-B6-Pad10)") (class "Default")
      (node (ref "U4") (pin "10") (pinfunction "B6_10") (pintype "bidirectional"))
    )
  )
)
